# Signal_Generation.net
KiCad netlist of a schematic drawn in EAGLE
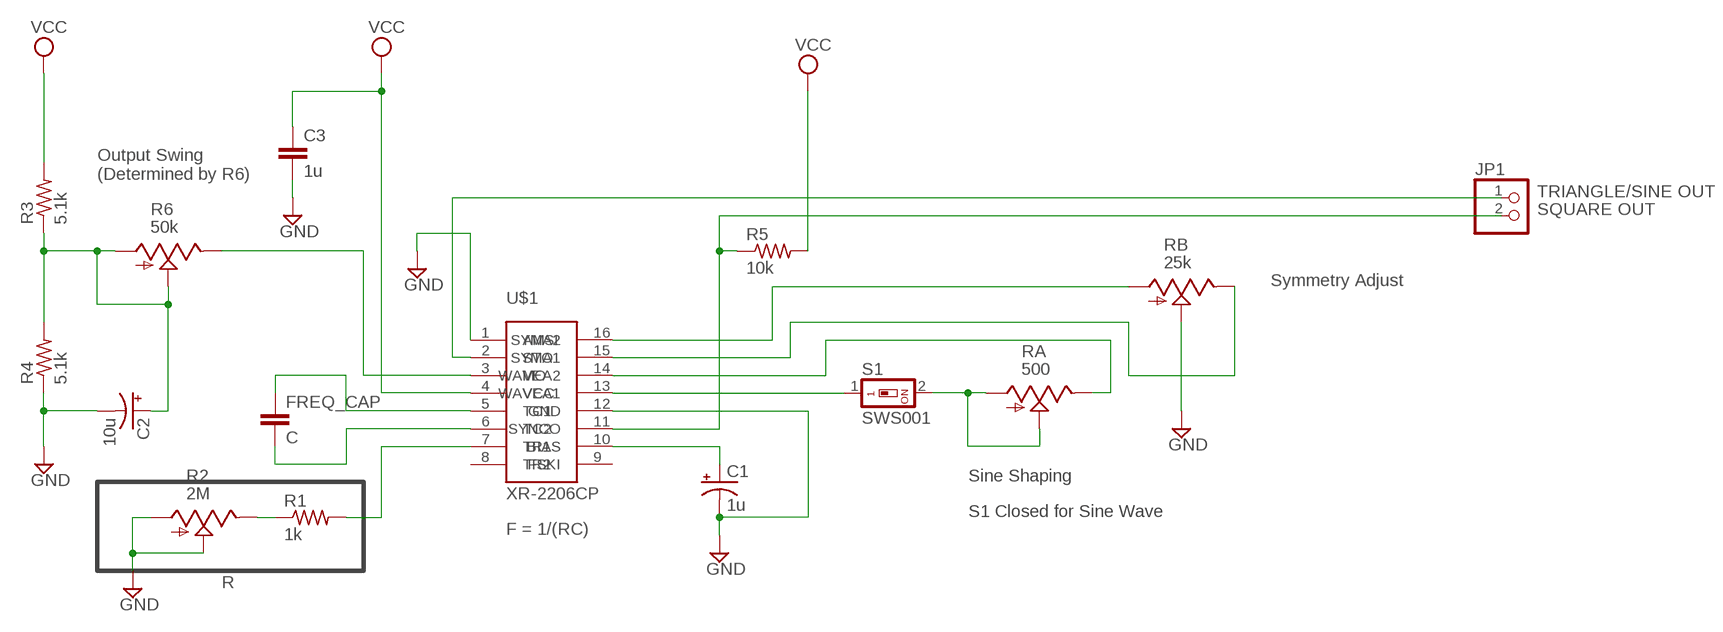
[diagram p0: schematic, sheet 1]

(export (version "E")
  (design (tool "Eeschema 10.0.6"))
  (components
    (comp (ref "C1")
      (value "1u")
      (footprint "eagle-import:E2,5-6E")
      (libsource (lib "eagle-import") (part "CPOL-USE2,5-6E"))
    )
    (comp (ref "C2")
      (value "10u")
      (footprint "eagle-import:E2,5-6E")
      (libsource (lib "eagle-import") (part "CPOL-USE2,5-6E"))
    )
    (comp (ref "C3")
      (value "1u")
      (footprint "eagle-import:C2.5-3")
      (libsource (lib "eagle-import") (part "C2,5-3"))
    )
    (comp (ref "FREQ_CAP")
      (value "C")
      (footprint "eagle-import:C2.5-3")
      (libsource (lib "eagle-import") (part "C2,5-3"))
    )
    (comp (ref "JP1")
      (value "PINHD-1X2")
      (footprint "eagle-import:1X02")
      (libsource (lib "eagle-import") (part "PINHD-1X2"))
    )
    (comp (ref "R1")
      (value "1k")
      (footprint "eagle-import:0204_5")
      (libsource (lib "eagle-import") (part "R-US_0204/5"))
    )
    (comp (ref "R2")
      (value "2M")
      (footprint "eagle-import:3223G")
      (libsource (lib "eagle-import") (part "TRIM_US-3223G"))
    )
    (comp (ref "R3")
      (value "5.1k")
      (footprint "eagle-import:0204_5")
      (libsource (lib "eagle-import") (part "R-US_0204/5"))
    )
    (comp (ref "R4")
      (value "5.1k")
      (footprint "eagle-import:0204_5")
      (libsource (lib "eagle-import") (part "R-US_0204/5"))
    )
    (comp (ref "R5")
      (value "10k")
      (footprint "eagle-import:0204_5")
      (libsource (lib "eagle-import") (part "R-US_0204/5"))
    )
    (comp (ref "R6")
      (value "50k")
      (footprint "eagle-import:3223G")
      (libsource (lib "eagle-import") (part "TRIM_US-3223G"))
    )
    (comp (ref "RA")
      (value "500")
      (footprint "eagle-import:3223G")
      (libsource (lib "eagle-import") (part "TRIM_US-3223G"))
    )
    (comp (ref "RB")
      (value "25k")
      (footprint "eagle-import:3223G")
      (libsource (lib "eagle-import") (part "TRIM_US-3223G"))
    )
    (comp (ref "S1")
      (value "SWS001")
      (footprint "eagle-import:SMS-001")
      (libsource (lib "eagle-import") (part "SWS001"))
    )
    (comp (ref "U$1")
      (value "XR-2206CP")
      (footprint "eagle-import:SOIC")
      (libsource (lib "eagle-import") (part "XR-2206CP"))
    )
  )
  (nets
    (net (code "1") (name "GND") (class "Default")
      (node (ref "C1") (pin "-") (pinfunction "-_-") (pintype "passive"))
      (node (ref "C2") (pin "-") (pinfunction "-_-") (pintype "passive"))
      (node (ref "C3") (pin "2") (pinfunction "2_2") (pintype "passive"))
      (node (ref "R2") (pin "1") (pinfunction "A_1") (pintype "passive"))
      (node (ref "R2") (pin "2") (pinfunction "S_2") (pintype "passive"))
      (node (ref "R4") (pin "1") (pinfunction "1_1") (pintype "passive"))
      (node (ref "RB") (pin "2") (pinfunction "S_2") (pintype "passive"))
      (node (ref "U$1") (pin "1") (pinfunction "AMSI_1") (pintype "input"))
      (node (ref "U$1") (pin "12") (pinfunction "GND_12") (pintype "power_in"))
    )
    (net (code "2") (name "Net-(R2-E)") (class "Default")
      (node (ref "R1") (pin "1") (pinfunction "1_1") (pintype "passive"))
      (node (ref "R2") (pin "3") (pinfunction "E_3") (pintype "passive"))
    )
    (net (code "3") (name "Net-(R6-A)") (class "Default")
      (node (ref "C2") (pin "+") (pinfunction "+_+") (pintype "passive"))
      (node (ref "R3") (pin "1") (pinfunction "1_1") (pintype "passive"))
      (node (ref "R4") (pin "2") (pinfunction "2_2") (pintype "passive"))
      (node (ref "R6") (pin "1") (pinfunction "A_1") (pintype "passive"))
      (node (ref "R6") (pin "2") (pinfunction "S_2") (pintype "passive"))
    )
    (net (code "4") (name "Net-(R6-E)") (class "Default")
      (node (ref "R6") (pin "3") (pinfunction "E_3") (pintype "passive"))
      (node (ref "U$1") (pin "3") (pinfunction "MO_3") (pintype "output"))
    )
    (net (code "5") (name "Net-(RA-A)") (class "Default")
      (node (ref "RA") (pin "1") (pinfunction "A_1") (pintype "passive"))
      (node (ref "RA") (pin "2") (pinfunction "S_2") (pintype "passive"))
      (node (ref "S1") (pin "2") (pinfunction "2_2") (pintype "passive"))
    )
    (net (code "6") (name "Net-(RA-E)") (class "Default")
      (node (ref "RA") (pin "3") (pinfunction "E_3") (pintype "passive"))
      (node (ref "U$1") (pin "14") (pinfunction "WAVEA2_14") (pintype "input"))
    )
    (net (code "7") (name "Net-(RB-A)") (class "Default")
      (node (ref "RB") (pin "1") (pinfunction "A_1") (pintype "passive"))
      (node (ref "U$1") (pin "16") (pinfunction "SYMA2_16") (pintype "input"))
    )
    (net (code "8") (name "Net-(RB-E)") (class "Default")
      (node (ref "RB") (pin "3") (pinfunction "E_3") (pintype "passive"))
      (node (ref "U$1") (pin "15") (pinfunction "SYMA1_15") (pintype "input"))
    )
    (net (code "9") (name "Net-(U$1-BIAS)") (class "Default")
      (node (ref "C1") (pin "+") (pinfunction "+_+") (pintype "passive"))
      (node (ref "U$1") (pin "10") (pinfunction "BIAS_10") (pintype "output"))
    )
    (net (code "10") (name "Net-(U$1-STO)") (class "Default")
      (node (ref "JP1") (pin "1") (pinfunction "1_1") (pintype "passive"))
      (node (ref "U$1") (pin "2") (pinfunction "STO_2") (pintype "output"))
    )
    (net (code "11") (name "Net-(U$1-SYNCO)") (class "Default")
      (node (ref "JP1") (pin "2") (pinfunction "2_2") (pintype "passive"))
      (node (ref "R5") (pin "1") (pinfunction "1_1") (pintype "passive"))
      (node (ref "U$1") (pin "11") (pinfunction "SYNCO_11") (pintype "output"))
    )
    (net (code "12") (name "Net-(U$1-TC1)") (class "Default")
      (node (ref "FREQ_CAP") (pin "1") (pinfunction "1_1") (pintype "passive"))
      (node (ref "U$1") (pin "5") (pinfunction "TC1_5") (pintype "input"))
    )
    (net (code "13") (name "Net-(U$1-TC2)") (class "Default")
      (node (ref "FREQ_CAP") (pin "2") (pinfunction "2_2") (pintype "passive"))
      (node (ref "U$1") (pin "6") (pinfunction "TC2_6") (pintype "input"))
    )
    (net (code "14") (name "Net-(U$1-TR1)") (class "Default")
      (node (ref "R1") (pin "2") (pinfunction "2_2") (pintype "passive"))
      (node (ref "U$1") (pin "7") (pinfunction "TR1_7") (pintype "output"))
    )
    (net (code "15") (name "Net-(U$1-WAVEA1)") (class "Default")
      (node (ref "S1") (pin "1") (pinfunction "1_1") (pintype "passive"))
      (node (ref "U$1") (pin "13") (pinfunction "WAVEA1_13") (pintype "input"))
    )
    (net (code "16") (name "VCC") (class "Default")
      (node (ref "C3") (pin "1") (pinfunction "1_1") (pintype "passive"))
      (node (ref "R3") (pin "2") (pinfunction "2_2") (pintype "passive"))
      (node (ref "R5") (pin "2") (pinfunction "2_2") (pintype "passive"))
      (node (ref "U$1") (pin "4") (pinfunction "VCC_4") (pintype "power_in"))
    )
    (net (code "17") (name "unconnected-(U$1-FSKI-Pad9)") (class "Default")
      (node (ref "U$1") (pin "9") (pinfunction "FSKI_9") (pintype "input"))
    )
    (net (code "18") (name "unconnected-(U$1-TR2-Pad8)") (class "Default")
      (node (ref "U$1") (pin "8") (pinfunction "TR2_8") (pintype "output"))
    )
  )
)
